# Sensor_Suite_2.net
KiCad netlist of a schematic drawn in Altium Designer
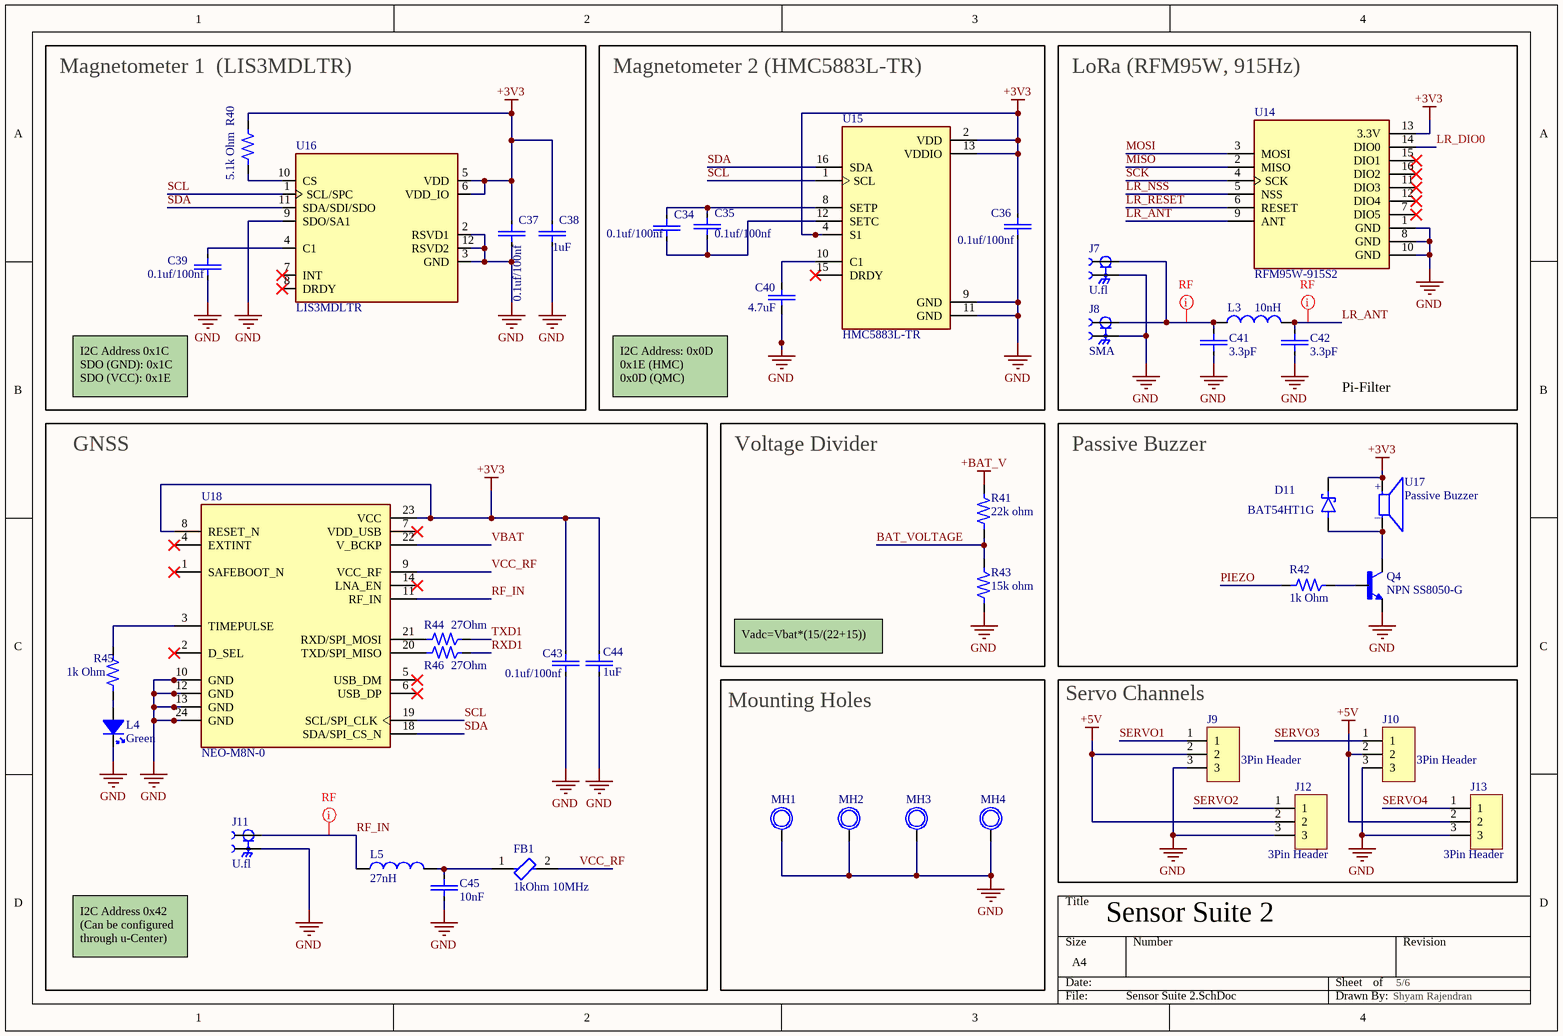
[diagram p0: Sensor Suite 2.SchDoc]

(export (version "E")
  (design (tool "Eeschema 10.0.6"))
  (components
    (comp (ref "C34")
      (value "0.1uf/100nf")
      (footprint "0.1uF Capacitor")
      (description "0.1 uF, Multilayer Ceramic Capacitor, 50 V, ï¿½ 10%, X7R, 0805 [2012 Metric]")
      (fields
        (field (name "MANUFACTURER") "Yageo")
        (field (name "MANUFACTURER PART NUMBER") "CC0805KRX7R9BB104")
      )
      (libsource (lib "Sirius") (part "CC0805KRX7R9BB104"))
    )
    (comp (ref "C35")
      (value "0.1uf/100nf")
      (footprint "0.1uF Capacitor")
      (description "0.1 uF, Multilayer Ceramic Capacitor, 50 V, ï¿½ 10%, X7R, 0805 [2012 Metric]")
      (fields
        (field (name "MANUFACTURER") "Yageo")
        (field (name "MANUFACTURER PART NUMBER") "CC0805KRX7R9BB104")
      )
      (libsource (lib "Sirius") (part "CC0805KRX7R9BB104"))
    )
    (comp (ref "C36")
      (value "0.1uf/100nf")
      (footprint "0.1uF Capacitor")
      (description "0.1 uF, Multilayer Ceramic Capacitor, 50 V, ï¿½ 10%, X7R, 0805 [2012 Metric]")
      (fields
        (field (name "MANUFACTURER") "Yageo")
        (field (name "MANUFACTURER PART NUMBER") "CC0805KRX7R9BB104")
      )
      (libsource (lib "Sirius") (part "CC0805KRX7R9BB104"))
    )
    (comp (ref "C37")
      (value "0.1uf/100nf")
      (footprint "0.1uF Capacitor")
      (description "0.1 uF, Multilayer Ceramic Capacitor, 50 V, ï¿½ 10%, X7R, 0805 [2012 Metric]")
      (fields
        (field (name "MANUFACTURER") "Yageo")
        (field (name "MANUFACTURER PART NUMBER") "CC0805KRX7R9BB104")
      )
      (libsource (lib "Sirius") (part "CC0805KRX7R9BB104"))
    )
    (comp (ref "C38")
      (value "1uF")
      (footprint "10uf Capacitor")
      (fields
        (field (name "MANUFACTURER") "Yageo")
        (field (name "MANUFACTURER PART NUMBER") "CC0805KKX7R6BB105")
      )
      (libsource (lib "Sirius") (part "CC0805KKX7R6BB105"))
    )
    (comp (ref "C39")
      (value "0.1uf/100nf")
      (footprint "0.1uF Capacitor")
      (description "0.1 uF, Multilayer Ceramic Capacitor, 50 V, ï¿½ 10%, X7R, 0805 [2012 Metric]")
      (fields
        (field (name "MANUFACTURER") "Yageo")
        (field (name "MANUFACTURER PART NUMBER") "CC0805KRX7R9BB104")
      )
      (libsource (lib "Sirius") (part "CC0805KRX7R9BB104"))
    )
    (comp (ref "C40")
      (value "4.7uF")
      (footprint "1k 0805 Resistor")
      (description "0603, 25V")
      (libsource (lib "Sirius") (part "4.7uF Capacitor"))
    )
    (comp (ref "C41")
      (value "3.3pF")
      (footprint "3.3pF")
      (description "0402")
      (libsource (lib "Sirius") (part "3.3pF Capacitor"))
    )
    (comp (ref "C42")
      (value "3.3pF")
      (footprint "3.3pF")
      (description "0402")
      (libsource (lib "Sirius") (part "3.3pF Capacitor"))
    )
    (comp (ref "C43")
      (value "0.1uf/100nf")
      (footprint "0.1uF Capacitor")
      (description "0.1 uF, Multilayer Ceramic Capacitor, 50 V, ï¿½ 10%, X7R, 0805 [2012 Metric]")
      (fields
        (field (name "MANUFACTURER") "Yageo")
        (field (name "MANUFACTURER PART NUMBER") "CC0805KRX7R9BB104")
      )
      (libsource (lib "Sirius") (part "CC0805KRX7R9BB104"))
    )
    (comp (ref "C44")
      (value "1uF")
      (footprint "10uf Capacitor")
      (fields
        (field (name "MANUFACTURER") "Yageo")
        (field (name "MANUFACTURER PART NUMBER") "CC0805KKX7R6BB105")
      )
      (libsource (lib "Sirius") (part "CC0805KKX7R6BB105"))
    )
    (comp (ref "C45") (value "10nF") (footprint "3.3pF") (libsource (lib "Sirius") (part "10nf Capacitor")))
    (comp (ref "D11")
      (value "BAT54HT1G")
      (footprint "SOD2513X110N")
      (fields (field (name "MF") "Infineon Technologies") (field (name "MP") "BAS3010A03WE6327HTSA1"))
      (libsource (lib "Sirius") (part "BAT54HT1G"))
    )
    (comp (ref "FB1")
      (value "1kOhm 10MHz")
      (footprint "1kOhm Ferrite bead 0402")
      (description "Ferrite Beads Multi-Layer 1KOhm 25% 100MHz 600mA 270mOhm DCR 0805 T/R")
      (fields
        (field (name "MANUFACTURER") "Murata")
        (field (name "MANUFACTURER PART NUMBER") "BLM21AG102SN1D")
      )
      (libsource (lib "Sirius") (part "BLM21AG102SN1D"))
    )
    (comp (ref "J7")
      (value "U.fl")
      (footprint "U.fl")
      (description "ufl connector")
      (fields (field (name "MP") "CONUFL001-SMD-T"))
      (libsource (lib "Sirius") (part "U.fl"))
    )
    (comp (ref "J8")
      (value "SMA")
      (footprint "SMA_CONNECTOR")
      (description "Straight SMA Connector")
      (fields (field (name "MP") "altium_native_batch"))
      (libsource (lib "Sirius") (part "SMA_CONNECTOR"))
    )
    (comp (ref "J9")
      (value "3Pin Header")
      (footprint "3 Pin Header")
      (libsource (lib "Sirius") (part "Header 3pin"))
    )
    (comp (ref "J10")
      (value "3Pin Header")
      (footprint "3 Pin Header")
      (libsource (lib "Sirius") (part "Header 3pin"))
    )
    (comp (ref "J11")
      (value "U.fl")
      (footprint "U.fl")
      (description "ufl connector")
      (fields (field (name "MP") "CONUFL001-SMD-T"))
      (libsource (lib "Sirius") (part "U.fl"))
    )
    (comp (ref "J12")
      (value "3Pin Header")
      (footprint "3 Pin Header")
      (libsource (lib "Sirius") (part "Header 3pin"))
    )
    (comp (ref "J13")
      (value "3Pin Header")
      (footprint "3 Pin Header")
      (libsource (lib "Sirius") (part "Header 3pin"))
    )
    (comp (ref "L3")
      (value "10nH")
      (footprint "0402 10nH")
      (description "0402")
      (libsource (lib "Sirius") (part "10nH Inductor"))
    )
    (comp (ref "L4")
      (value "Green")
      (footprint "LED Green")
      (description "Green 0805")
      (libsource (lib "Sirius") (part "LED Green"))
    )
    (comp (ref "L5")
      (value "27nH")
      (footprint "0402 10nH")
      (description "0402")
      (libsource (lib "Sirius") (part "27nH Inductor"))
    )
    (comp (ref "MH1")
      (value "PMH 3.0")
      (footprint "PMH")
      (description "PMH 3.0mm")
      (libsource (lib "Sirius") (part "PMH"))
    )
    (comp (ref "MH2")
      (value "PMH 3.0")
      (footprint "PMH")
      (description "PMH 3.0mm")
      (libsource (lib "Sirius") (part "PMH"))
    )
    (comp (ref "MH3")
      (value "PMH 3.0")
      (footprint "PMH")
      (description "PMH 3.0mm")
      (libsource (lib "Sirius") (part "PMH"))
    )
    (comp (ref "MH4")
      (value "PMH 3.0")
      (footprint "PMH")
      (description "PMH 3.0mm")
      (libsource (lib "Sirius") (part "PMH"))
    )
    (comp (ref "Q4")
      (value "NPN SS8050-G")
      (footprint "Transistor_SS8050-G")
      (description "Trans Gp Bjt NPN 25V 1.5A 300MW 3-PIN SOT-23 T/r")
      (fields (field (name "MANUFACTURER") "Comchip") (field (name "MANUFACTURER PART NUMBER") "SS8050-G"))
      (libsource (lib "Sirius") (part "SS8050-G"))
    )
    (comp (ref "R40")
      (value "5.1k Ohm")
      (footprint "RESC2012X60N")
      (description "5.1k Ohm, 0805, 0.125W, 150V, 1% +/-Tol, 100ppm/Cel, Surface Mount")
      (fields
        (field (name "MANUFACTURER") "Yageo")
        (field (name "MANUFACTURER PART NUMBER") "RC0805FR-075K1L")
      )
      (libsource (lib "Sirius") (part "RC0805FR-075K1L"))
    )
    (comp (ref "R41")
      (value "22k ohm")
      (footprint "1k 0805 Resistor")
      (description "0805")
      (libsource (lib "Sirius") (part "22k Resistor"))
    )
    (comp (ref "R42")
      (value "1k Ohm")
      (footprint "1k 0805 Resistor")
      (description "1k Ohm, 0805, SMD Chip Resistor , ï¿½ 1%, 125 mW,[2012 Metric], Thick Film, General Purpose")
      (fields
        (field (name "MANUFACTURER") "Yageo")
        (field (name "MANUFACTURER PART NUMBER") "RC0805FR-071KL")
      )
      (libsource (lib "Sirius") (part "RC0805FR-071KL"))
    )
    (comp (ref "R43")
      (value "15k ohm")
      (footprint "1k 0805 Resistor")
      (description "0805")
      (libsource (lib "Sirius") (part "15k Resistor"))
    )
    (comp (ref "R44")
      (value "27Ohm")
      (footprint "1k 0805 Resistor")
      (description "27 Ohm, Res Thin Film 0805 1% 1/8W ±50ppm/°C Molded SMD SMD Paper T/R")
      (fields
        (field (name "MANUFACTURER") "Yageo")
        (field (name "MANUFACTURER PART NUMBER") "RT0805FRE0727RL")
      )
      (libsource (lib "Sirius") (part "RT0805FRE0727RL"))
    )
    (comp (ref "R45")
      (value "1k Ohm")
      (footprint "1k 0805 Resistor")
      (description "1k Ohm, 0805, SMD Chip Resistor , ï¿½ 1%, 125 mW,[2012 Metric], Thick Film, General Purpose")
      (fields
        (field (name "MANUFACTURER") "Yageo")
        (field (name "MANUFACTURER PART NUMBER") "RC0805FR-071KL")
      )
      (libsource (lib "Sirius") (part "RC0805FR-071KL"))
    )
    (comp (ref "R46")
      (value "27Ohm")
      (footprint "1k 0805 Resistor")
      (description "27 Ohm, Res Thin Film 0805 1% 1/8W ±50ppm/°C Molded SMD SMD Paper T/R")
      (fields
        (field (name "MANUFACTURER") "Yageo")
        (field (name "MANUFACTURER PART NUMBER") "RT0805FRE0727RL")
      )
      (libsource (lib "Sirius") (part "RT0805FRE0727RL"))
    )
    (comp (ref "U14")
      (value "RFM95W-915S2")
      (footprint "RFM95W-915S2")
      (description "RFM95(W) - Low Power Long Range Transceiver Module V1.0")
      (libsource (lib "Sirius") (part "RFM95W-915S2"))
    )
    (comp (ref "U15")
      (value "HMC5883L-TR")
      (footprint "HMC5883L-TR")
      (fields (field (name "MF") "STMicroelectronics") (field (name "MP") "HMC5883LTR"))
      (libsource (lib "Sirius") (part "HMC5883L-TR"))
    )
    (comp (ref "U16")
      (value "LIS3MDLTR")
      (footprint "LIS3MDLTR")
      (description "Magnetoresistive Sensor X, Y, Z Axis 12-LGA _2x2_")
      (fields (field (name "MF") "STMicroelectronics"))
      (libsource (lib "Sirius") (part "LIS3MDLTR"))
    )
    (comp (ref "U17")
      (value "Passive Buzzer")
      (footprint "BuzzerCMT-7525-80-SMT-TR")
      (description "7.5 mm, 3.6 Vo-p, 80 dB, Surface Mount (SMT), Magnetic Audio Transducer Buzzer")
      (fields
        (field (name "DIGI-KEY_PART_NUMBER") "102-CMT-7525-80-SMT-TR-ND")
        (field (name "MF") "CUI Devices")
      )
      (libsource (lib "Sirius") (part "Buzzer CMT-7525-80-SMT-TR"))
    )
    (comp (ref "U18")
      (value "NEO-M8N-0")
      (footprint "NEO-M8N-0")
      (description "Ic Receiver Gps/Gnss 24lcc")
      (libsource (lib "Sirius") (part "NEO-M8N-0"))
    )
  )
  (nets
    (net (code "1") (name "+3V3") (class "Default")
      (node (ref "C36") (pin "2") (pinfunction "2_2") (pintype "passive"))
      (node (ref "C37") (pin "2") (pinfunction "2_2") (pintype "passive"))
      (node (ref "C38") (pin "2") (pinfunction "2_2") (pintype "passive"))
      (node (ref "C43") (pin "2") (pinfunction "2_2") (pintype "passive"))
      (node (ref "C44") (pin "2") (pinfunction "2_2") (pintype "passive"))
      (node (ref "D11") (pin "C") (pinfunction "K_C") (pintype "passive"))
      (node (ref "R40") (pin "2") (pinfunction "2_2") (pintype "passive"))
      (node (ref "U14") (pin "13") (pinfunction "3.3V_13") (pintype "passive"))
      (node (ref "U15") (pin "13") (pinfunction "VDDIO_13") (pintype "passive"))
      (node (ref "U15") (pin "2") (pinfunction "VDD_2") (pintype "passive"))
      (node (ref "U15") (pin "4") (pinfunction "S1_4") (pintype "passive"))
      (node (ref "U16") (pin "5") (pinfunction "VDD_5") (pintype "passive"))
      (node (ref "U16") (pin "6") (pinfunction "VDD_IO_6") (pintype "passive"))
      (node (ref "U17") (pin "P") (pinfunction "P_P") (pintype "passive"))
      (node (ref "U18") (pin "23") (pinfunction "VCC_23") (pintype "passive"))
      (node (ref "U18") (pin "8") (pinfunction "RESET_N_8") (pintype "passive"))
    )
    (net (code "2") (name "+5V") (class "Default")
      (node (ref "J10") (pin "2") (pinfunction "2_2") (pintype "passive"))
      (node (ref "J12") (pin "2") (pinfunction "2_2") (pintype "passive"))
      (node (ref "J13") (pin "2") (pinfunction "2_2") (pintype "passive"))
      (node (ref "J9") (pin "2") (pinfunction "2_2") (pintype "passive"))
    )
    (net (code "3") (name "+BAT_V") (class "Default")
      (node (ref "R41") (pin "2") (pinfunction "2_2") (pintype "passive"))
    )
    (net (code "4") (name "/BAT_VOLTAGE") (class "Default")
      (node (ref "R41") (pin "1") (pinfunction "1_1") (pintype "passive"))
      (node (ref "R43") (pin "2") (pinfunction "2_2") (pintype "passive"))
    )
    (net (code "5") (name "/LR_ANT") (class "Default")
      (node (ref "C42") (pin "2") (pinfunction "2_2") (pintype "passive"))
      (node (ref "L3") (pin "2") (pinfunction "2_2") (pintype "passive"))
      (node (ref "U14") (pin "9") (pinfunction "ANT_9") (pintype "passive"))
    )
    (net (code "6") (name "/LR_DIO0") (class "Default")
      (node (ref "U14") (pin "14") (pinfunction "DIO0_14") (pintype "passive"))
    )
    (net (code "7") (name "/LR_NSS") (class "Default")
      (node (ref "U14") (pin "5") (pinfunction "NSS_5") (pintype "passive"))
    )
    (net (code "8") (name "/LR_RESET") (class "Default")
      (node (ref "U14") (pin "6") (pinfunction "RESET_6") (pintype "passive"))
    )
    (net (code "9") (name "/MISO") (class "Default")
      (node (ref "U14") (pin "2") (pinfunction "MISO_2") (pintype "passive"))
    )
    (net (code "10") (name "/MOSI") (class "Default")
      (node (ref "U14") (pin "3") (pinfunction "MOSI_3") (pintype "passive"))
    )
    (net (code "11") (name "/PIEZO") (class "Default")
      (node (ref "R42") (pin "1") (pinfunction "1_1") (pintype "passive"))
    )
    (net (code "12") (name "/RF_IN") (class "Default")
      (node (ref "J11") (pin "1") (pinfunction "1_1") (pintype "passive"))
      (node (ref "L5") (pin "1") (pinfunction "1_1") (pintype "passive"))
      (node (ref "U18") (pin "11") (pinfunction "RF_IN_11") (pintype "passive"))
    )
    (net (code "13") (name "/RXD1") (class "Default")
      (node (ref "R46") (pin "2") (pinfunction "2_2") (pintype "passive"))
    )
    (net (code "14") (name "/SCK") (class "Default")
      (node (ref "U14") (pin "4") (pinfunction "SCK_4") (pintype "passive"))
    )
    (net (code "15") (name "/SCL") (class "Default")
      (node (ref "U15") (pin "1") (pinfunction "SCL_1") (pintype "passive"))
      (node (ref "U16") (pin "1") (pinfunction "SCL/SPC_1") (pintype "passive"))
      (node (ref "U18") (pin "19") (pinfunction "SCL/SPI_CLK_19") (pintype "passive"))
    )
    (net (code "16") (name "/SDA") (class "Default")
      (node (ref "U15") (pin "16") (pinfunction "SDA_16") (pintype "passive"))
      (node (ref "U16") (pin "11") (pinfunction "SDA/SDI/SDO_11") (pintype "passive"))
      (node (ref "U18") (pin "18") (pinfunction "SDA/SPI_CS_N_18") (pintype "passive"))
    )
    (net (code "17") (name "/SERVO1") (class "Default")
      (node (ref "J9") (pin "1") (pinfunction "1_1") (pintype "passive"))
    )
    (net (code "18") (name "/SERVO2") (class "Default")
      (node (ref "J12") (pin "1") (pinfunction "1_1") (pintype "passive"))
    )
    (net (code "19") (name "/SERVO3") (class "Default")
      (node (ref "J10") (pin "1") (pinfunction "1_1") (pintype "passive"))
    )
    (net (code "20") (name "/SERVO4") (class "Default")
      (node (ref "J13") (pin "1") (pinfunction "1_1") (pintype "passive"))
    )
    (net (code "21") (name "/TXD1") (class "Default")
      (node (ref "R44") (pin "2") (pinfunction "2_2") (pintype "passive"))
    )
    (net (code "22") (name "/VBAT") (class "Default")
      (node (ref "U18") (pin "22") (pinfunction "V_BCKP_22") (pintype "passive"))
    )
    (net (code "23") (name "/VCC_RF") (class "Default")
      (node (ref "FB1") (pin "2") (pinfunction "2_2") (pintype "passive"))
      (node (ref "U18") (pin "9") (pinfunction "VCC_RF_9") (pintype "passive"))
    )
    (net (code "24") (name "GND") (class "Default")
      (node (ref "C36") (pin "1") (pinfunction "1_1") (pintype "passive"))
      (node (ref "C37") (pin "1") (pinfunction "1_1") (pintype "passive"))
      (node (ref "C38") (pin "1") (pinfunction "1_1") (pintype "passive"))
      (node (ref "C39") (pin "1") (pinfunction "1_1") (pintype "passive"))
      (node (ref "C40") (pin "1") (pinfunction "1_1") (pintype "passive"))
      (node (ref "C41") (pin "1") (pinfunction "1_1") (pintype "passive"))
      (node (ref "C42") (pin "1") (pinfunction "1_1") (pintype "passive"))
      (node (ref "C43") (pin "1") (pinfunction "1_1") (pintype "passive"))
      (node (ref "C44") (pin "1") (pinfunction "1_1") (pintype "passive"))
      (node (ref "C45") (pin "1") (pinfunction "1_1") (pintype "passive"))
      (node (ref "J10") (pin "3") (pinfunction "3_3") (pintype "passive"))
      (node (ref "J11") (pin "GND") (pinfunction "GND_GND") (pintype "passive"))
      (node (ref "J12") (pin "3") (pinfunction "3_3") (pintype "passive"))
      (node (ref "J13") (pin "3") (pinfunction "3_3") (pintype "passive"))
      (node (ref "J7") (pin "GND") (pinfunction "GND_GND") (pintype "passive"))
      (node (ref "J8") (pin "GND") (pinfunction "GND_GND") (pintype "passive"))
      (node (ref "J9") (pin "3") (pinfunction "3_3") (pintype "passive"))
      (node (ref "L4") (pin "C") (pinfunction "2_C") (pintype "passive"))
      (node (ref "MH1") (pin "GND") (pinfunction "GND_GND") (pintype "passive"))
      (node (ref "MH2") (pin "GND") (pinfunction "GND_GND") (pintype "passive"))
      (node (ref "MH3") (pin "GND") (pinfunction "GND_GND") (pintype "passive"))
      (node (ref "MH4") (pin "GND") (pinfunction "GND_GND") (pintype "passive"))
      (node (ref "Q4") (pin "2") (pinfunction "E_2") (pintype "passive"))
      (node (ref "R43") (pin "1") (pinfunction "1_1") (pintype "passive"))
      (node (ref "U14") (pin "1") (pinfunction "GND_1") (pintype "passive"))
      (node (ref "U14") (pin "10") (pinfunction "GND_10") (pintype "passive"))
      (node (ref "U14") (pin "8") (pinfunction "GND_8") (pintype "passive"))
      (node (ref "U15") (pin "11") (pinfunction "GND_11") (pintype "passive"))
      (node (ref "U15") (pin "9") (pinfunction "GND_9") (pintype "passive"))
      (node (ref "U16") (pin "12") (pinfunction "RSVD2_12") (pintype "passive"))
      (node (ref "U16") (pin "2") (pinfunction "RSVD1_2") (pintype "passive"))
      (node (ref "U16") (pin "3") (pinfunction "GND_3") (pintype "passive"))
      (node (ref "U16") (pin "9") (pinfunction "SDO/SA1_9") (pintype "passive"))
      (node (ref "U18") (pin "10") (pinfunction "GND_10") (pintype "passive"))
      (node (ref "U18") (pin "12") (pinfunction "GND_12") (pintype "passive"))
      (node (ref "U18") (pin "13") (pinfunction "GND_13") (pintype "passive"))
      (node (ref "U18") (pin "24") (pinfunction "GND_24") (pintype "passive"))
    )
    (net (code "25") (name "Net-(C41-Pad2)") (class "Default")
      (node (ref "C41") (pin "2") (pinfunction "2_2") (pintype "passive"))
      (node (ref "J7") (pin "1") (pinfunction "1_1") (pintype "passive"))
      (node (ref "J8") (pin "1") (pinfunction "1_1") (pintype "passive"))
      (node (ref "L3") (pin "1") (pinfunction "1_1") (pintype "passive"))
    )
    (net (code "26") (name "Net-(C45-Pad2)") (class "Default")
      (node (ref "C45") (pin "2") (pinfunction "2_2") (pintype "passive"))
      (node (ref "FB1") (pin "1") (pinfunction "1_1") (pintype "passive"))
      (node (ref "L5") (pin "2") (pinfunction "2_2") (pintype "passive"))
    )
    (net (code "27") (name "Net-(L4-1)") (class "Default")
      (node (ref "L4") (pin "A") (pinfunction "1_A") (pintype "passive"))
      (node (ref "R45") (pin "1") (pinfunction "1_1") (pintype "passive"))
    )
    (net (code "28") (name "Net-(Q4-B)") (class "Default")
      (node (ref "Q4") (pin "1") (pinfunction "B_1") (pintype "passive"))
      (node (ref "R42") (pin "2") (pinfunction "2_2") (pintype "passive"))
    )
    (net (code "29") (name "Net-(Q4-C)") (class "Default")
      (node (ref "D11") (pin "A") (pinfunction "A_A") (pintype "passive"))
      (node (ref "Q4") (pin "3") (pinfunction "C_3") (pintype "passive"))
      (node (ref "U17") (pin "N") (pinfunction "N_N") (pintype "passive"))
    )
    (net (code "30") (name "Net-(U15-C1)") (class "Default")
      (node (ref "C40") (pin "2") (pinfunction "2_2") (pintype "passive"))
      (node (ref "U15") (pin "10") (pinfunction "C1_10") (pintype "passive"))
    )
    (net (code "31") (name "Net-(U15-SETC)") (class "Default")
      (node (ref "C34") (pin "1") (pinfunction "1_1") (pintype "passive"))
      (node (ref "C35") (pin "1") (pinfunction "1_1") (pintype "passive"))
      (node (ref "U15") (pin "12") (pinfunction "SETC_12") (pintype "passive"))
    )
    (net (code "32") (name "Net-(U15-SETP)") (class "Default")
      (node (ref "C34") (pin "2") (pinfunction "2_2") (pintype "passive"))
      (node (ref "C35") (pin "2") (pinfunction "2_2") (pintype "passive"))
      (node (ref "U15") (pin "8") (pinfunction "SETP_8") (pintype "passive"))
    )
    (net (code "33") (name "Net-(U16-C1)") (class "Default")
      (node (ref "C39") (pin "2") (pinfunction "2_2") (pintype "passive"))
      (node (ref "U16") (pin "4") (pinfunction "C1_4") (pintype "passive"))
    )
    (net (code "34") (name "Net-(U16-CS)") (class "Default")
      (node (ref "R40") (pin "1") (pinfunction "1_1") (pintype "passive"))
      (node (ref "U16") (pin "10") (pinfunction "CS_10") (pintype "passive"))
    )
    (net (code "35") (name "Net-(U18-RXD{slash}SPI_MOSI)") (class "Default")
      (node (ref "R44") (pin "1") (pinfunction "1_1") (pintype "passive"))
      (node (ref "U18") (pin "21") (pinfunction "RXD/SPI_MOSI_21") (pintype "passive"))
    )
    (net (code "36") (name "Net-(U18-TIMEPULSE)") (class "Default")
      (node (ref "R45") (pin "2") (pinfunction "2_2") (pintype "passive"))
      (node (ref "U18") (pin "3") (pinfunction "TIMEPULSE_3") (pintype "passive"))
    )
    (net (code "37") (name "Net-(U18-TXD{slash}SPI_MISO)") (class "Default")
      (node (ref "R46") (pin "1") (pinfunction "1_1") (pintype "passive"))
      (node (ref "U18") (pin "20") (pinfunction "TXD/SPI_MISO_20") (pintype "passive"))
    )
    (net (code "38") (name "unconnected-(U14-DIO1-Pad15)") (class "Default")
      (node (ref "U14") (pin "15") (pinfunction "DIO1_15") (pintype "passive+no_connect"))
    )
    (net (code "39") (name "unconnected-(U14-DIO2-Pad16)") (class "Default")
      (node (ref "U14") (pin "16") (pinfunction "DIO2_16") (pintype "passive+no_connect"))
    )
    (net (code "40") (name "unconnected-(U14-DIO3-Pad11)") (class "Default")
      (node (ref "U14") (pin "11") (pinfunction "DIO3_11") (pintype "passive+no_connect"))
    )
    (net (code "41") (name "unconnected-(U14-DIO4-Pad12)") (class "Default")
      (node (ref "U14") (pin "12") (pinfunction "DIO4_12") (pintype "passive+no_connect"))
    )
    (net (code "42") (name "unconnected-(U14-DIO5-Pad7)") (class "Default")
      (node (ref "U14") (pin "7") (pinfunction "DIO5_7") (pintype "passive+no_connect"))
    )
    (net (code "43") (name "unconnected-(U15-DRDY-Pad15)") (class "Default")
      (node (ref "U15") (pin "15") (pinfunction "DRDY_15") (pintype "passive+no_connect"))
    )
    (net (code "44") (name "unconnected-(U16-DRDY-Pad8)") (class "Default")
      (node (ref "U16") (pin "8") (pinfunction "DRDY_8") (pintype "passive+no_connect"))
    )
    (net (code "45") (name "unconnected-(U16-INT-Pad7)") (class "Default")
      (node (ref "U16") (pin "7") (pinfunction "INT_7") (pintype "passive+no_connect"))
    )
    (net (code "46") (name "unconnected-(U18-D_SEL-Pad2)") (class "Default")
      (node (ref "U18") (pin "2") (pinfunction "D_SEL_2") (pintype "passive+no_connect"))
    )
    (net (code "47") (name "unconnected-(U18-EXTINT-Pad4)") (class "Default")
      (node (ref "U18") (pin "4") (pinfunction "EXTINT_4") (pintype "passive+no_connect"))
    )
    (net (code "48") (name "unconnected-(U18-LNA_EN-Pad14)") (class "Default")
      (node (ref "U18") (pin "14") (pinfunction "LNA_EN_14") (pintype "passive+no_connect"))
    )
    (net (code "49") (name "unconnected-(U18-SAFEBOOT_N-Pad1)") (class "Default")
      (node (ref "U18") (pin "1") (pinfunction "SAFEBOOT_N_1") (pintype "passive+no_connect"))
    )
    (net (code "50") (name "unconnected-(U18-USB_DM-Pad5)") (class "Default")
      (node (ref "U18") (pin "5") (pinfunction "USB_DM_5") (pintype "passive+no_connect"))
    )
    (net (code "51") (name "unconnected-(U18-USB_DP-Pad6)") (class "Default")
      (node (ref "U18") (pin "6") (pinfunction "USB_DP_6") (pintype "passive+no_connect"))
    )
    (net (code "52") (name "unconnected-(U18-VDD_USB-Pad7)") (class "Default")
      (node (ref "U18") (pin "7") (pinfunction "VDD_USB_7") (pintype "passive+no_connect"))
    )
  )
)
